# DSO150_Conversion_Board_2_1.net
KiCad netlist of a schematic drawn in EAGLE
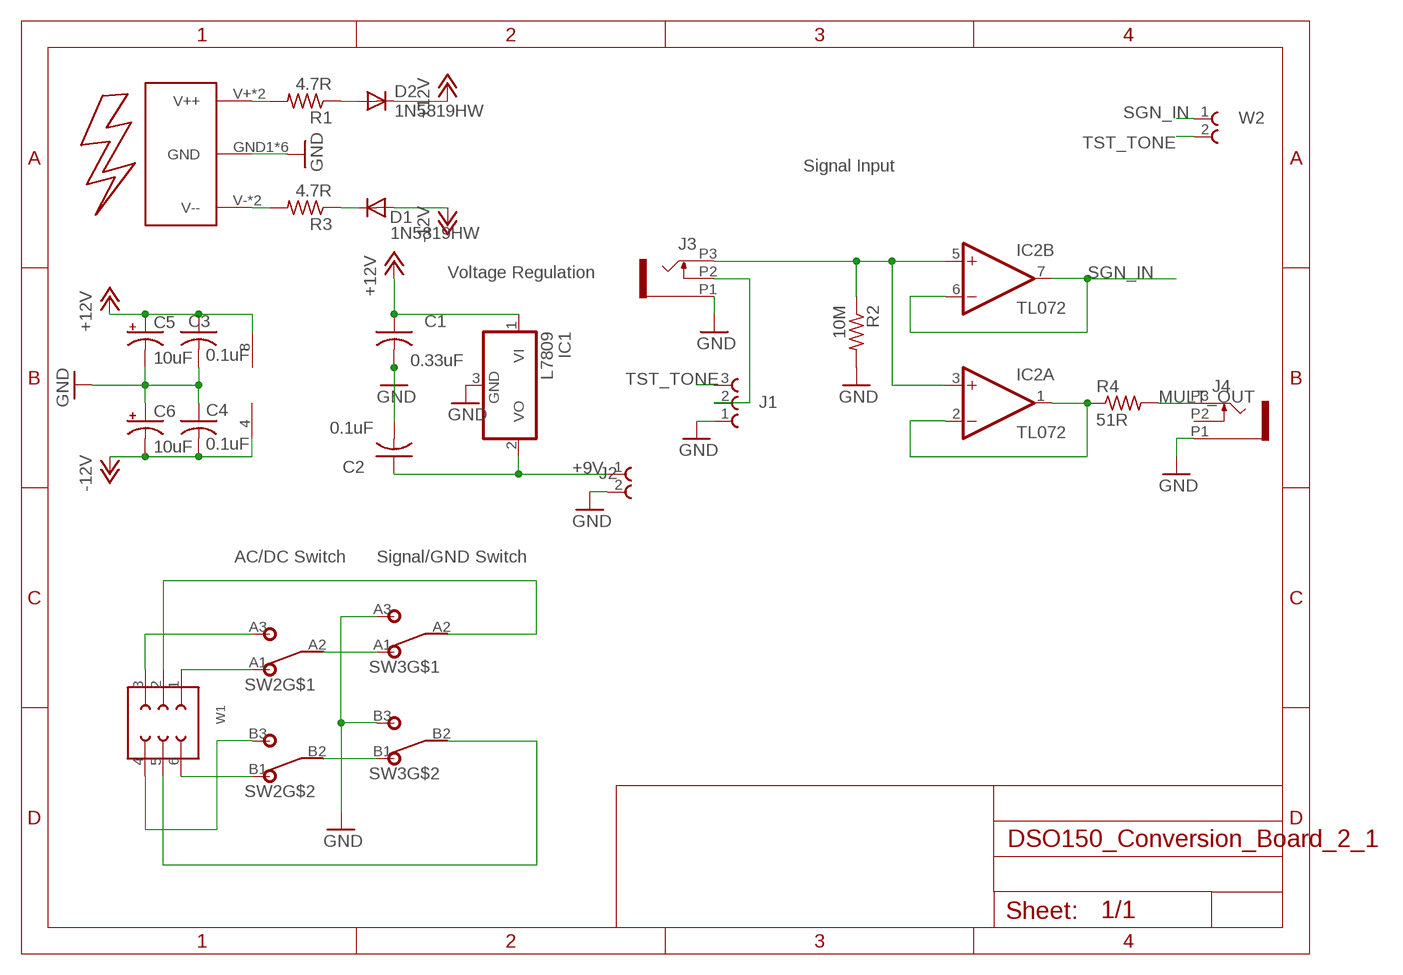
[diagram p0: schematic, sheet 1]

(export (version "E")
  (design (tool "Eeschema 10.0.6"))
  (components
    (comp (ref "C1")
      (value "0.33uF")
      (footprint "eagle-import:C0805")
      (libsource (lib "eagle-import") (part "C-USC0805"))
    )
    (comp (ref "C2")
      (value "0.1uF")
      (footprint "eagle-import:C0805")
      (libsource (lib "eagle-import") (part "C-USC0805"))
    )
    (comp (ref "C3")
      (value "0.1uF")
      (footprint "eagle-import:C0805")
      (libsource (lib "eagle-import") (part "C-USC0805"))
    )
    (comp (ref "C4")
      (value "0.1uF")
      (footprint "eagle-import:C0805")
      (libsource (lib "eagle-import") (part "C-USC0805"))
    )
    (comp (ref "C5")
      (value "10uF")
      (footprint "eagle-import:PANASONIC_B")
      (libsource (lib "eagle-import") (part "CPOL-USB"))
    )
    (comp (ref "C6")
      (value "10uF")
      (footprint "eagle-import:PANASONIC_B")
      (libsource (lib "eagle-import") (part "CPOL-USB"))
    )
    (comp (ref "D1")
      (value "1N5819HW")
      (footprint "eagle-import:DIODE_SOD123")
      (libsource (lib "eagle-import") (part "DIODE_DIODE-SOD123"))
    )
    (comp (ref "D2")
      (value "1N5819HW")
      (footprint "eagle-import:DIODE_SOD123")
      (libsource (lib "eagle-import") (part "DIODE_DIODE-SOD123"))
    )
    (comp (ref "IC1")
      (value "L7809")
      (footprint "eagle-import:TO252")
      (libsource (lib "eagle-import") (part "78DT08"))
    )
    (comp (ref "IC2")
      (value "TL072")
      (footprint "eagle-import:SO08")
      (libsource (lib "eagle-import") (part "TL072D"))
    )
    (comp (ref "J1")
      (value "61300311121")
      (footprint "eagle-import:61300311121")
      (libsource (lib "eagle-import") (part "61300311121"))
    )
    (comp (ref "J2")
      (value "61300211121")
      (footprint "eagle-import:61300211121")
      (libsource (lib "eagle-import") (part "61300211121"))
    )
    (comp (ref "J3")
      (value "OG-PJ301_PJ301_THONKICONN7")
      (footprint "eagle-import:OG-PJ301_WQP_PJ_301M7")
      (libsource (lib "eagle-import") (part "OG-PJ301_PJ301_THONKICONN7"))
    )
    (comp (ref "J4")
      (value "OG-PJ301_PJ301_THONKICONN7")
      (footprint "eagle-import:OG-PJ301_WQP_PJ_301M7")
      (libsource (lib "eagle-import") (part "OG-PJ301_PJ301_THONKICONN7"))
    )
    (comp (ref "R1")
      (value "4.7R")
      (footprint "eagle-import:R1206")
      (libsource (lib "eagle-import") (part "R-US_R1206"))
    )
    (comp (ref "R2")
      (value "10M")
      (footprint "eagle-import:R0805")
      (libsource (lib "eagle-import") (part "R-US_R0805"))
    )
    (comp (ref "R3")
      (value "4.7R")
      (footprint "eagle-import:R1206")
      (libsource (lib "eagle-import") (part "R-US_R1206"))
    )
    (comp (ref "R4")
      (value "51R")
      (footprint "eagle-import:R0805")
      (libsource (lib "eagle-import") (part "R-US_R0805"))
    )
    (comp (ref "SW2")
      (value "SUBDPDT")
      (footprint "eagle-import:SUBMINIDPDT")
      (libsource (lib "eagle-import") (part "SUBDPDT"))
    )
    (comp (ref "SW3")
      (value "SUBDPDT")
      (footprint "eagle-import:SUBMINIDPDT")
      (libsource (lib "eagle-import") (part "SUBDPDT"))
    )
    (comp (ref "U$2")
      (value "EURO_POWER2")
      (footprint "eagle-import:EURO_POWER2")
      (libsource (lib "eagle-import") (part "EURO_POWER2"))
    )
    (comp (ref "W1")
      (value "61300621121")
      (footprint "eagle-import:61300621121")
      (libsource (lib "eagle-import") (part "61300621121"))
    )
    (comp (ref "W2")
      (value "61300211121")
      (footprint "eagle-import:61300211121")
      (libsource (lib "eagle-import") (part "61300211121"))
    )
  )
  (nets
    (net (code "1") (name "+12V") (class "Default")
      (node (ref "C1") (pin "1") (pinfunction "1_1") (pintype "passive"))
      (node (ref "C3") (pin "1") (pinfunction "1_1") (pintype "passive"))
      (node (ref "C5") (pin "+") (pinfunction "+_+") (pintype "passive"))
      (node (ref "D2") (pin "C") (pinfunction "C_C") (pintype "passive"))
      (node (ref "IC1") (pin "1") (pinfunction "VI_1") (pintype "input"))
      (node (ref "IC2") (pin "8") (pinfunction "V+_8") (pintype "power_in"))
    )
    (net (code "2") (name "-12V") (class "Default")
      (node (ref "C4") (pin "2") (pinfunction "2_2") (pintype "passive"))
      (node (ref "C6") (pin "-") (pinfunction "-_-") (pintype "passive"))
      (node (ref "D1") (pin "A") (pinfunction "A_A") (pintype "passive"))
      (node (ref "IC2") (pin "4") (pinfunction "V-_4") (pintype "power_in"))
    )
    (net (code "3") (name "/+9V") (class "Default")
      (node (ref "C2") (pin "1") (pinfunction "1_1") (pintype "passive"))
      (node (ref "IC1") (pin "2") (pinfunction "VO_2") (pintype "passive"))
      (node (ref "J2") (pin "1") (pinfunction "1_1") (pintype "passive"))
    )
    (net (code "4") (name "/MULT_OUT") (class "Default")
      (node (ref "IC2") (pin "1") (pinfunction "OUT_1") (pintype "output"))
      (node (ref "IC2") (pin "2") (pinfunction "-IN_2") (pintype "input"))
      (node (ref "R4") (pin "1") (pinfunction "1_1") (pintype "passive"))
    )
    (net (code "5") (name "/SGN_IN") (class "Default")
      (node (ref "IC2") (pin "6") (pinfunction "-IN_6") (pintype "input"))
      (node (ref "IC2") (pin "7") (pinfunction "OUT_7") (pintype "output"))
      (node (ref "W2") (pin "1") (pinfunction "1_1") (pintype "passive"))
    )
    (net (code "6") (name "/TST_TONE") (class "Default")
      (node (ref "J1") (pin "3") (pinfunction "1_3") (pintype "passive"))
      (node (ref "W2") (pin "2") (pinfunction "2_2") (pintype "passive"))
    )
    (net (code "7") (name "GND") (class "Default")
      (node (ref "C1") (pin "2") (pinfunction "2_2") (pintype "passive"))
      (node (ref "C2") (pin "2") (pinfunction "2_2") (pintype "passive"))
      (node (ref "C3") (pin "2") (pinfunction "2_2") (pintype "passive"))
      (node (ref "C4") (pin "1") (pinfunction "1_1") (pintype "passive"))
      (node (ref "C5") (pin "-") (pinfunction "-_-") (pintype "passive"))
      (node (ref "C6") (pin "+") (pinfunction "+_+") (pintype "passive"))
      (node (ref "IC1") (pin "3") (pinfunction "GND_3") (pintype "passive"))
      (node (ref "J1") (pin "1") (pinfunction "3_1") (pintype "passive"))
      (node (ref "J2") (pin "2") (pinfunction "2_2") (pintype "passive"))
      (node (ref "J3") (pin "P1") (pinfunction "1_P1") (pintype "passive"))
      (node (ref "J4") (pin "P1") (pinfunction "1_P1") (pintype "passive"))
      (node (ref "R2") (pin "2") (pinfunction "2_2") (pintype "passive"))
      (node (ref "SW3") (pin "A3") (pinfunction "3_A3") (pintype "passive"))
      (node (ref "SW3") (pin "B3") (pinfunction "3_B3") (pintype "passive"))
      (node (ref "U$2") (pin "GND1") (pinfunction "GND_GND1") (pintype "bidirectional"))
      (node (ref "U$2") (pin "GND2") (pinfunction "GND_GND2") (pintype "bidirectional"))
      (node (ref "U$2") (pin "GND3") (pinfunction "GND_GND3") (pintype "bidirectional"))
      (node (ref "U$2") (pin "GND4") (pinfunction "GND_GND4") (pintype "bidirectional"))
      (node (ref "U$2") (pin "GND5") (pinfunction "GND_GND5") (pintype "bidirectional"))
      (node (ref "U$2") (pin "GND6") (pinfunction "GND_GND6") (pintype "bidirectional"))
    )
    (net (code "8") (name "Net-(D1-PadC)") (class "Default")
      (node (ref "D1") (pin "C") (pinfunction "C_C") (pintype "passive"))
      (node (ref "R3") (pin "1") (pinfunction "1_1") (pintype "passive"))
    )
    (net (code "9") (name "Net-(D2-PadA)") (class "Default")
      (node (ref "D2") (pin "A") (pinfunction "A_A") (pintype "passive"))
      (node (ref "R1") (pin "1") (pinfunction "1_1") (pintype "passive"))
    )
    (net (code "10") (name "Net-(IC2A-+IN)") (class "Default")
      (node (ref "IC2") (pin "3") (pinfunction "+IN_3") (pintype "input"))
      (node (ref "IC2") (pin "5") (pinfunction "+IN_5") (pintype "input"))
      (node (ref "J3") (pin "P3") (pinfunction "3_P3") (pintype "passive"))
      (node (ref "R2") (pin "1") (pinfunction "1_1") (pintype "passive"))
    )
    (net (code "11") (name "Net-(J3-2)") (class "Default")
      (node (ref "J1") (pin "2") (pinfunction "2_2") (pintype "passive"))
      (node (ref "J3") (pin "P2") (pinfunction "2_P2") (pintype "passive"))
    )
    (net (code "12") (name "Net-(J4-3)") (class "Default")
      (node (ref "J4") (pin "P3") (pinfunction "3_P3") (pintype "passive"))
      (node (ref "R4") (pin "2") (pinfunction "2_2") (pintype "passive"))
    )
    (net (code "13") (name "Net-(R1-Pad2)") (class "Default")
      (node (ref "R1") (pin "2") (pinfunction "2_2") (pintype "passive"))
      (node (ref "U$2") (pin "V+") (pinfunction "V++_V+") (pintype "bidirectional"))
      (node (ref "U$2") (pin "V++") (pinfunction "V++_V++") (pintype "bidirectional"))
    )
    (net (code "14") (name "Net-(R3-Pad2)") (class "Default")
      (node (ref "R3") (pin "2") (pinfunction "2_2") (pintype "passive"))
      (node (ref "U$2") (pin "V-") (pinfunction "V--_V-") (pintype "bidirectional"))
      (node (ref "U$2") (pin "V--") (pinfunction "V--_V--") (pintype "bidirectional"))
    )
    (net (code "15") (name "Net-(SW2A-1)") (class "Default")
      (node (ref "SW2") (pin "A1") (pinfunction "1_A1") (pintype "passive"))
      (node (ref "W1") (pin "1") (pinfunction "1_1") (pintype "passive"))
    )
    (net (code "16") (name "Net-(SW2A-2)") (class "Default")
      (node (ref "SW2") (pin "A2") (pinfunction "2_A2") (pintype "passive"))
      (node (ref "SW3") (pin "A1") (pinfunction "1_A1") (pintype "passive"))
    )
    (net (code "17") (name "Net-(SW2A-3)") (class "Default")
      (node (ref "SW2") (pin "A3") (pinfunction "3_A3") (pintype "passive"))
      (node (ref "W1") (pin "3") (pinfunction "3_3") (pintype "passive"))
    )
    (net (code "18") (name "Net-(SW2B-1)") (class "Default")
      (node (ref "SW2") (pin "B1") (pinfunction "1_B1") (pintype "passive"))
      (node (ref "W1") (pin "6") (pinfunction "6_6") (pintype "passive"))
    )
    (net (code "19") (name "Net-(SW2B-2)") (class "Default")
      (node (ref "SW2") (pin "B2") (pinfunction "2_B2") (pintype "passive"))
      (node (ref "SW3") (pin "B1") (pinfunction "1_B1") (pintype "passive"))
    )
    (net (code "20") (name "Net-(SW2B-3)") (class "Default")
      (node (ref "SW2") (pin "B3") (pinfunction "3_B3") (pintype "passive"))
      (node (ref "W1") (pin "4") (pinfunction "4_4") (pintype "passive"))
    )
    (net (code "21") (name "Net-(SW3A-2)") (class "Default")
      (node (ref "SW3") (pin "A2") (pinfunction "2_A2") (pintype "passive"))
      (node (ref "W1") (pin "2") (pinfunction "2_2") (pintype "passive"))
    )
    (net (code "22") (name "Net-(SW3B-2)") (class "Default")
      (node (ref "SW3") (pin "B2") (pinfunction "2_B2") (pintype "passive"))
      (node (ref "W1") (pin "5") (pinfunction "5_5") (pintype "passive"))
    )
    (net (code "23") (name "unconnected-(J4-2-PadP2)") (class "Default")
      (node (ref "J4") (pin "P2") (pinfunction "2_P2") (pintype "passive"))
    )
  )
)
